# SourceFollower_SOT23_Modular.net
KiCad netlist of a schematic drawn in Altium Designer
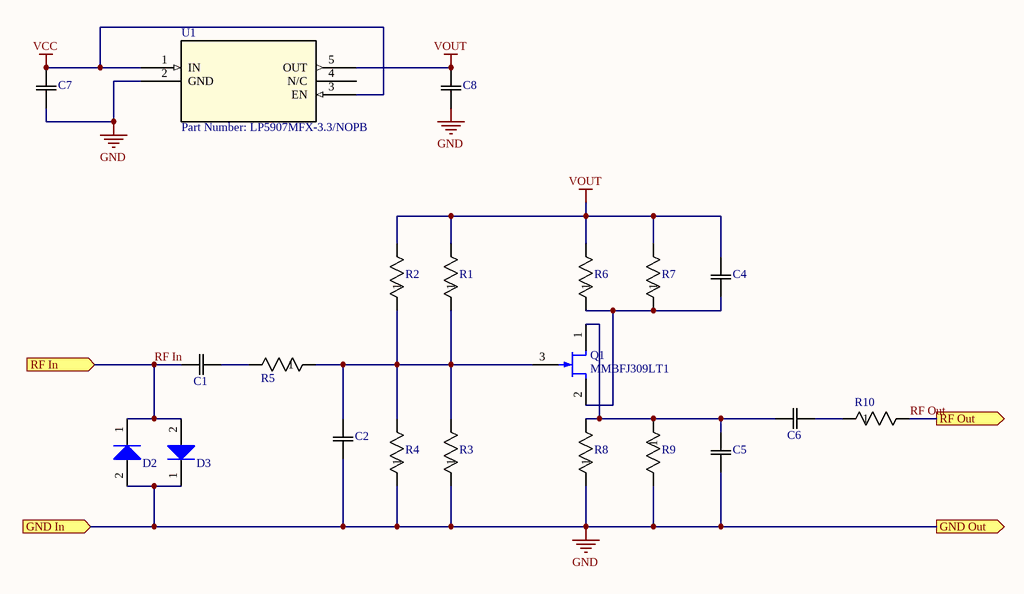
[diagram p0: SourceFollower_SOT23_Modular.SchDoc]

(export (version "E")
  (design (tool "Eeschema 10.0.6"))
  (components
    (comp (ref "C1")
      (value "Part Number: C0201C270J3GACTU")
      (footprint "C0201")
      (description "No Description Available")
      (fields
        (field (name "MANUFACTURER_PART_NUMBER") "C0201C270J3GACTU")
        (field (name "COPYRIGHT") "Copyright (C) 2018 Accelerated Designs. All rights reserved")
      )
      (libsource (lib "0201Capacitor_Yageo") (part "C0201C270J3GACTU"))
    )
    (comp (ref "C2")
      (value "Part Number: C0201C270J3GACTU")
      (footprint "C0201")
      (description "No Description Available")
      (fields
        (field (name "MANUFACTURER_PART_NUMBER") "C0201C270J3GACTU")
        (field (name "COPYRIGHT") "Copyright (C) 2018 Accelerated Designs. All rights reserved")
      )
      (libsource (lib "0201Capacitor_Yageo") (part "C0201C270J3GACTU"))
    )
    (comp (ref "C4")
      (value "Part Number: C0201C270J3GACTU")
      (footprint "C0201")
      (description "No Description Available")
      (fields
        (field (name "MANUFACTURER_PART_NUMBER") "C0201C270J3GACTU")
        (field (name "COPYRIGHT") "Copyright (C) 2018 Accelerated Designs. All rights reserved")
      )
      (libsource (lib "0201Capacitor_Yageo") (part "C0201C270J3GACTU"))
    )
    (comp (ref "C5")
      (value "Part Number: C0201C270J3GACTU")
      (footprint "C0201")
      (description "No Description Available")
      (fields
        (field (name "MANUFACTURER_PART_NUMBER") "C0201C270J3GACTU")
        (field (name "COPYRIGHT") "Copyright (C) 2018 Accelerated Designs. All rights reserved")
      )
      (libsource (lib "0201Capacitor_Yageo") (part "C0201C270J3GACTU"))
    )
    (comp (ref "C6")
      (value "Part Number: C0201C270J3GACTU")
      (footprint "C0201")
      (description "No Description Available")
      (fields
        (field (name "MANUFACTURER_PART_NUMBER") "C0201C270J3GACTU")
        (field (name "COPYRIGHT") "Copyright (C) 2018 Accelerated Designs. All rights reserved")
      )
      (libsource (lib "0201Capacitor_Yageo") (part "C0201C270J3GACTU"))
    )
    (comp (ref "C7")
      (value "Part Number: CC0402KRX7R6BB104")
      (footprint "YAG_CC0402")
      (description "No Description Available")
      (fields
        (field (name "MANUFACTURER_PART_NUMBER") "CC0402KRX7R6BB104")
        (field (name "COPYRIGHT") "Copyright (C) 2018 Accelerated Designs. All rights reserved")
      )
      (libsource (lib "0402Capacitor_Yageo") (part "CC0402KRX7R6BB10"))
    )
    (comp (ref "C8")
      (value "Part Number: CC0402KRX7R6BB104")
      (footprint "YAG_CC0402")
      (description "No Description Available")
      (fields
        (field (name "MANUFACTURER_PART_NUMBER") "CC0402KRX7R6BB104")
        (field (name "COPYRIGHT") "Copyright (C) 2018 Accelerated Designs. All rights reserved")
      )
      (libsource (lib "0402Capacitor_Yageo") (part "CC0402KRX7R6BB10"))
    )
    (comp (ref "D2")
      (value "BAT15-03W")
      (footprint "INF-SOD323_V")
      (description "Single Silicon Schottky Diode, 110 mA IF Max, SOD32, Green")
      (fields (field (name "MANUFACTURER") "Infineon"))
      (libsource (lib "Infineon_RFSchottkyDiode_SOD323") (part "BAT15-03W"))
    )
    (comp (ref "D3")
      (value "BAT15-03W")
      (footprint "INF-SOD323_V")
      (description "Single Silicon Schottky Diode, 110 mA IF Max, SOD32, Green")
      (fields (field (name "MANUFACTURER") "Infineon"))
      (libsource (lib "Infineon_RFSchottkyDiode_SOD323") (part "BAT15-03W"))
    )
    (comp (ref "Q1")
      (value "MMBFJ309LT1")
      (footprint "ONSC-SOT-23-3-318-08_V")
      (description "JFET - VHF / UHF Amplifier Transistor, N-Channel, 3-Pin SOT-23, Tape and Reel")
      (fields (field (name "MANUFACTURER") "On Semiconductor"))
      (libsource (lib "ON Semi JFETs") (part "MMBFJ309LT1"))
    )
    (comp (ref "R1")
      (value "Part Number: RC0201FR-0718KL")
      (footprint "RES_RC0201_P6XP3")
      (description "No Description Available")
      (fields
        (field (name "MANUFACTURER_PART_NUMBER") "RC0201FR-0718KL")
        (field (name "COPYRIGHT") "Copyright (C) 2018 Accelerated Designs. All rights reserved")
      )
      (libsource (lib "0201Resistor_Yageo") (part "RC0201FR-0718KL"))
    )
    (comp (ref "R2")
      (value "Part Number: RC0201FR-0718KL")
      (footprint "RES_RC0201_P6XP3")
      (description "No Description Available")
      (fields
        (field (name "MANUFACTURER_PART_NUMBER") "RC0201FR-0718KL")
        (field (name "COPYRIGHT") "Copyright (C) 2018 Accelerated Designs. All rights reserved")
      )
      (libsource (lib "0201Resistor_Yageo") (part "RC0201FR-0718KL"))
    )
    (comp (ref "R3")
      (value "Part Number: RC0201FR-0718KL")
      (footprint "RES_RC0201_P6XP3")
      (description "No Description Available")
      (fields
        (field (name "MANUFACTURER_PART_NUMBER") "RC0201FR-0718KL")
        (field (name "COPYRIGHT") "Copyright (C) 2018 Accelerated Designs. All rights reserved")
      )
      (libsource (lib "0201Resistor_Yageo") (part "RC0201FR-0718KL"))
    )
    (comp (ref "R4")
      (value "Part Number: RC0201FR-0718KL")
      (footprint "RES_RC0201_P6XP3")
      (description "No Description Available")
      (fields
        (field (name "MANUFACTURER_PART_NUMBER") "RC0201FR-0718KL")
        (field (name "COPYRIGHT") "Copyright (C) 2018 Accelerated Designs. All rights reserved")
      )
      (libsource (lib "0201Resistor_Yageo") (part "RC0201FR-0718KL"))
    )
    (comp (ref "R5")
      (value "Part Number: RC0201FR-0718KL")
      (footprint "RES_RC0201_P6XP3")
      (description "No Description Available")
      (fields
        (field (name "MANUFACTURER_PART_NUMBER") "RC0201FR-0718KL")
        (field (name "COPYRIGHT") "Copyright (C) 2018 Accelerated Designs. All rights reserved")
      )
      (libsource (lib "0201Resistor_Yageo") (part "RC0201FR-0718KL"))
    )
    (comp (ref "R6")
      (value "Part Number: RC0201FR-0718KL")
      (footprint "RES_RC0201_P6XP3")
      (description "No Description Available")
      (fields
        (field (name "MANUFACTURER_PART_NUMBER") "RC0201FR-0718KL")
        (field (name "COPYRIGHT") "Copyright (C) 2018 Accelerated Designs. All rights reserved")
      )
      (libsource (lib "0201Resistor_Yageo") (part "RC0201FR-0718KL"))
    )
    (comp (ref "R7")
      (value "Part Number: RC0201FR-0718KL")
      (footprint "RES_RC0201_P6XP3")
      (description "No Description Available")
      (fields
        (field (name "MANUFACTURER_PART_NUMBER") "RC0201FR-0718KL")
        (field (name "COPYRIGHT") "Copyright (C) 2018 Accelerated Designs. All rights reserved")
      )
      (libsource (lib "0201Resistor_Yageo") (part "RC0201FR-0718KL"))
    )
    (comp (ref "R8")
      (value "Part Number: RC0201FR-0718KL")
      (footprint "RES_RC0201_P6XP3")
      (description "No Description Available")
      (fields
        (field (name "MANUFACTURER_PART_NUMBER") "RC0201FR-0718KL")
        (field (name "COPYRIGHT") "Copyright (C) 2018 Accelerated Designs. All rights reserved")
      )
      (libsource (lib "0201Resistor_Yageo") (part "RC0201FR-0718KL"))
    )
    (comp (ref "R9")
      (value "Part Number: RC0201FR-0718KL")
      (footprint "RES_RC0201_P6XP3")
      (description "No Description Available")
      (fields
        (field (name "MANUFACTURER_PART_NUMBER") "RC0201FR-0718KL")
        (field (name "COPYRIGHT") "Copyright (C) 2018 Accelerated Designs. All rights reserved")
      )
      (libsource (lib "0201Resistor_Yageo") (part "RC0201FR-0718KL"))
    )
    (comp (ref "R10")
      (value "Part Number: RC0201FR-0718KL")
      (footprint "RES_RC0201_P6XP3")
      (description "No Description Available")
      (fields
        (field (name "MANUFACTURER_PART_NUMBER") "RC0201FR-0718KL")
        (field (name "COPYRIGHT") "Copyright (C) 2018 Accelerated Designs. All rights reserved")
      )
      (libsource (lib "0201Resistor_Yageo") (part "RC0201FR-0718KL"))
    )
    (comp (ref "U1")
      (value "Part Number: LP5907MFX-3.3/NOPB")
      (footprint "DBV5")
      (description "No Description Available")
      (fields
        (field (name "MANUFACTURER_PART_NUMBER") "LP5907MFX-3.3/NOPB")
        (field (name "COPYRIGHT") "Copyright (C) 2018 Accelerated Designs. All rights reserved")
      )
      (libsource (lib "TI_LDO_3V3_SOT325") (part "LP5907MFX-3.3/NO"))
    )
  )
  (nets
    (net (code "1") (name "/RF In") (class "Default")
      (node (ref "C1") (pin "1") (pinfunction "1_1") (pintype "passive"))
      (node (ref "D2") (pin "1") (pinfunction "K_1") (pintype "passive"))
      (node (ref "D3") (pin "2") (pinfunction "A_2") (pintype "passive"))
    )
    (net (code "2") (name "/RF Out") (class "Default")
      (node (ref "R10") (pin "2") (pinfunction "2_2") (pintype "passive"))
    )
    (net (code "3") (name "GND") (class "Default")
      (node (ref "C2") (pin "1") (pinfunction "1_1") (pintype "passive"))
      (node (ref "C5") (pin "1") (pinfunction "1_1") (pintype "passive"))
      (node (ref "C7") (pin "1") (pinfunction "1_1") (pintype "passive"))
      (node (ref "C8") (pin "1") (pinfunction "1_1") (pintype "passive"))
      (node (ref "D2") (pin "2") (pinfunction "A_2") (pintype "passive"))
      (node (ref "D3") (pin "1") (pinfunction "K_1") (pintype "passive"))
      (node (ref "R3") (pin "1") (pinfunction "1_1") (pintype "passive"))
      (node (ref "R4") (pin "1") (pinfunction "1_1") (pintype "passive"))
      (node (ref "R8") (pin "1") (pinfunction "1_1") (pintype "passive"))
      (node (ref "R9") (pin "2") (pinfunction "2_2") (pintype "passive"))
      (node (ref "U1") (pin "2") (pinfunction "GND_2") (pintype "power_in"))
    )
    (net (code "4") (name "Net-(C1-Pad2)") (class "Default")
      (node (ref "C1") (pin "2") (pinfunction "2_2") (pintype "passive"))
      (node (ref "R5") (pin "2") (pinfunction "2_2") (pintype "passive"))
    )
    (net (code "5") (name "Net-(C6-Pad1)") (class "Default")
      (node (ref "C6") (pin "1") (pinfunction "1_1") (pintype "passive"))
      (node (ref "R10") (pin "1") (pinfunction "1_1") (pintype "passive"))
    )
    (net (code "6") (name "Net-(Q1-D)") (class "Default")
      (node (ref "C5") (pin "2") (pinfunction "2_2") (pintype "passive"))
      (node (ref "C6") (pin "2") (pinfunction "2_2") (pintype "passive"))
      (node (ref "Q1") (pin "1") (pinfunction "D_1") (pintype "passive"))
      (node (ref "R8") (pin "2") (pinfunction "2_2") (pintype "passive"))
      (node (ref "R9") (pin "1") (pinfunction "1_1") (pintype "passive"))
    )
    (net (code "7") (name "Net-(Q1-G)") (class "Default")
      (node (ref "C2") (pin "2") (pinfunction "2_2") (pintype "passive"))
      (node (ref "Q1") (pin "3") (pinfunction "G_3") (pintype "passive"))
      (node (ref "R1") (pin "1") (pinfunction "1_1") (pintype "passive"))
      (node (ref "R2") (pin "1") (pinfunction "1_1") (pintype "passive"))
      (node (ref "R3") (pin "2") (pinfunction "2_2") (pintype "passive"))
      (node (ref "R4") (pin "2") (pinfunction "2_2") (pintype "passive"))
      (node (ref "R5") (pin "1") (pinfunction "1_1") (pintype "passive"))
    )
    (net (code "8") (name "Net-(Q1-S)") (class "Default")
      (node (ref "C4") (pin "1") (pinfunction "1_1") (pintype "passive"))
      (node (ref "Q1") (pin "2") (pinfunction "S_2") (pintype "passive"))
      (node (ref "R6") (pin "1") (pinfunction "1_1") (pintype "passive"))
      (node (ref "R7") (pin "1") (pinfunction "1_1") (pintype "passive"))
    )
    (net (code "9") (name "VCC") (class "Default")
      (node (ref "C7") (pin "2") (pinfunction "2_2") (pintype "passive"))
      (node (ref "U1") (pin "1") (pinfunction "IN_1") (pintype "input"))
      (node (ref "U1") (pin "3") (pinfunction "EN_3") (pintype "input"))
    )
    (net (code "10") (name "VOUT") (class "Default")
      (node (ref "C4") (pin "2") (pinfunction "2_2") (pintype "passive"))
      (node (ref "C8") (pin "2") (pinfunction "2_2") (pintype "passive"))
      (node (ref "R1") (pin "2") (pinfunction "2_2") (pintype "passive"))
      (node (ref "R2") (pin "2") (pinfunction "2_2") (pintype "passive"))
      (node (ref "R6") (pin "2") (pinfunction "2_2") (pintype "passive"))
      (node (ref "R7") (pin "2") (pinfunction "2_2") (pintype "passive"))
      (node (ref "U1") (pin "5") (pinfunction "OUT_5") (pintype "output"))
    )
    (net (code "11") (name "unconnected-(U1-N{slash}C-Pad4)") (class "Default")
      (node (ref "U1") (pin "4") (pinfunction "N/C_4") (pintype "passive"))
    )
  )
)
